# KarateLight-exp.net
KiCad netlist of a schematic drawn in EAGLE
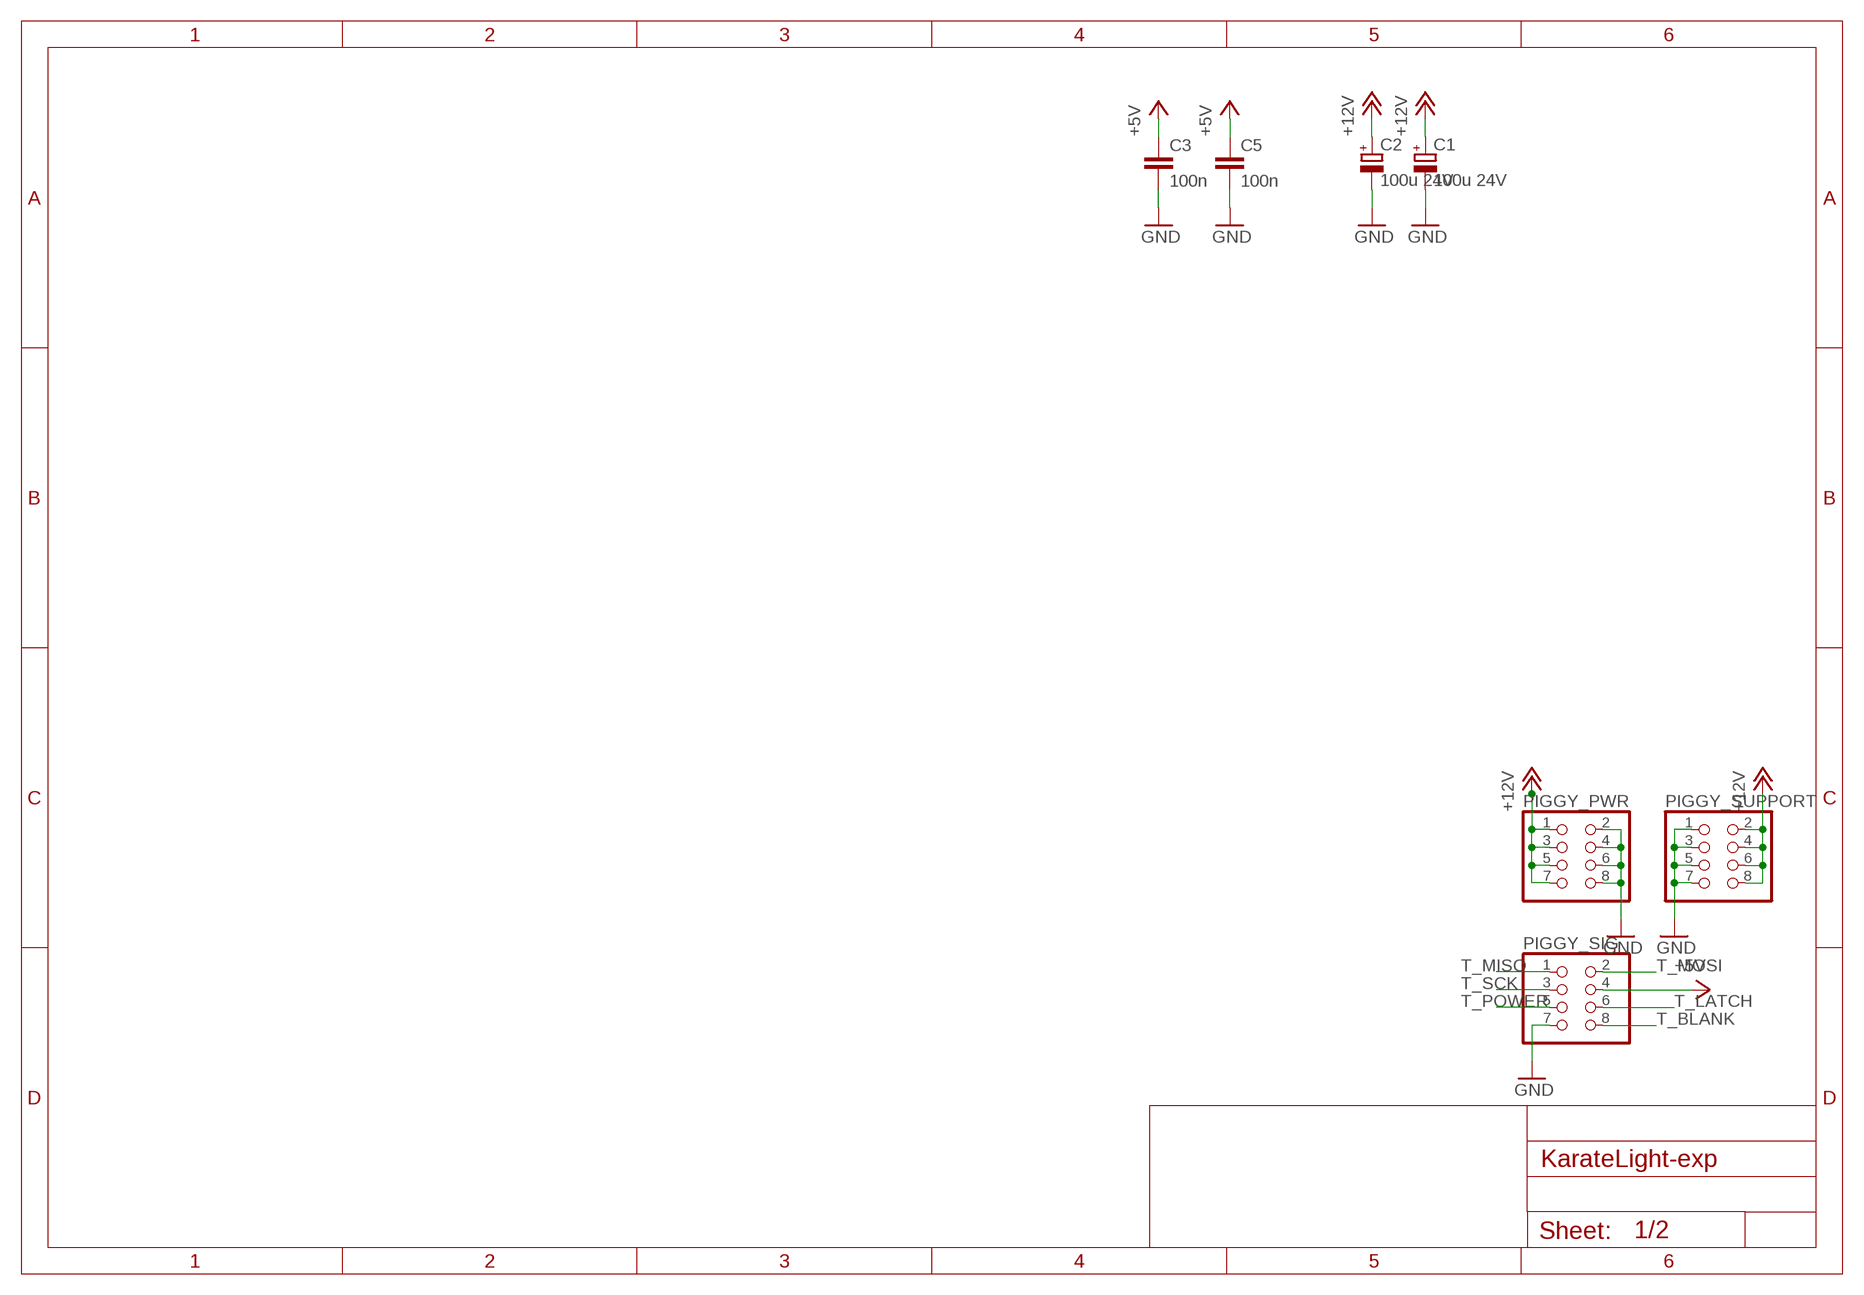
[diagram p0: schematic, sheet 1]
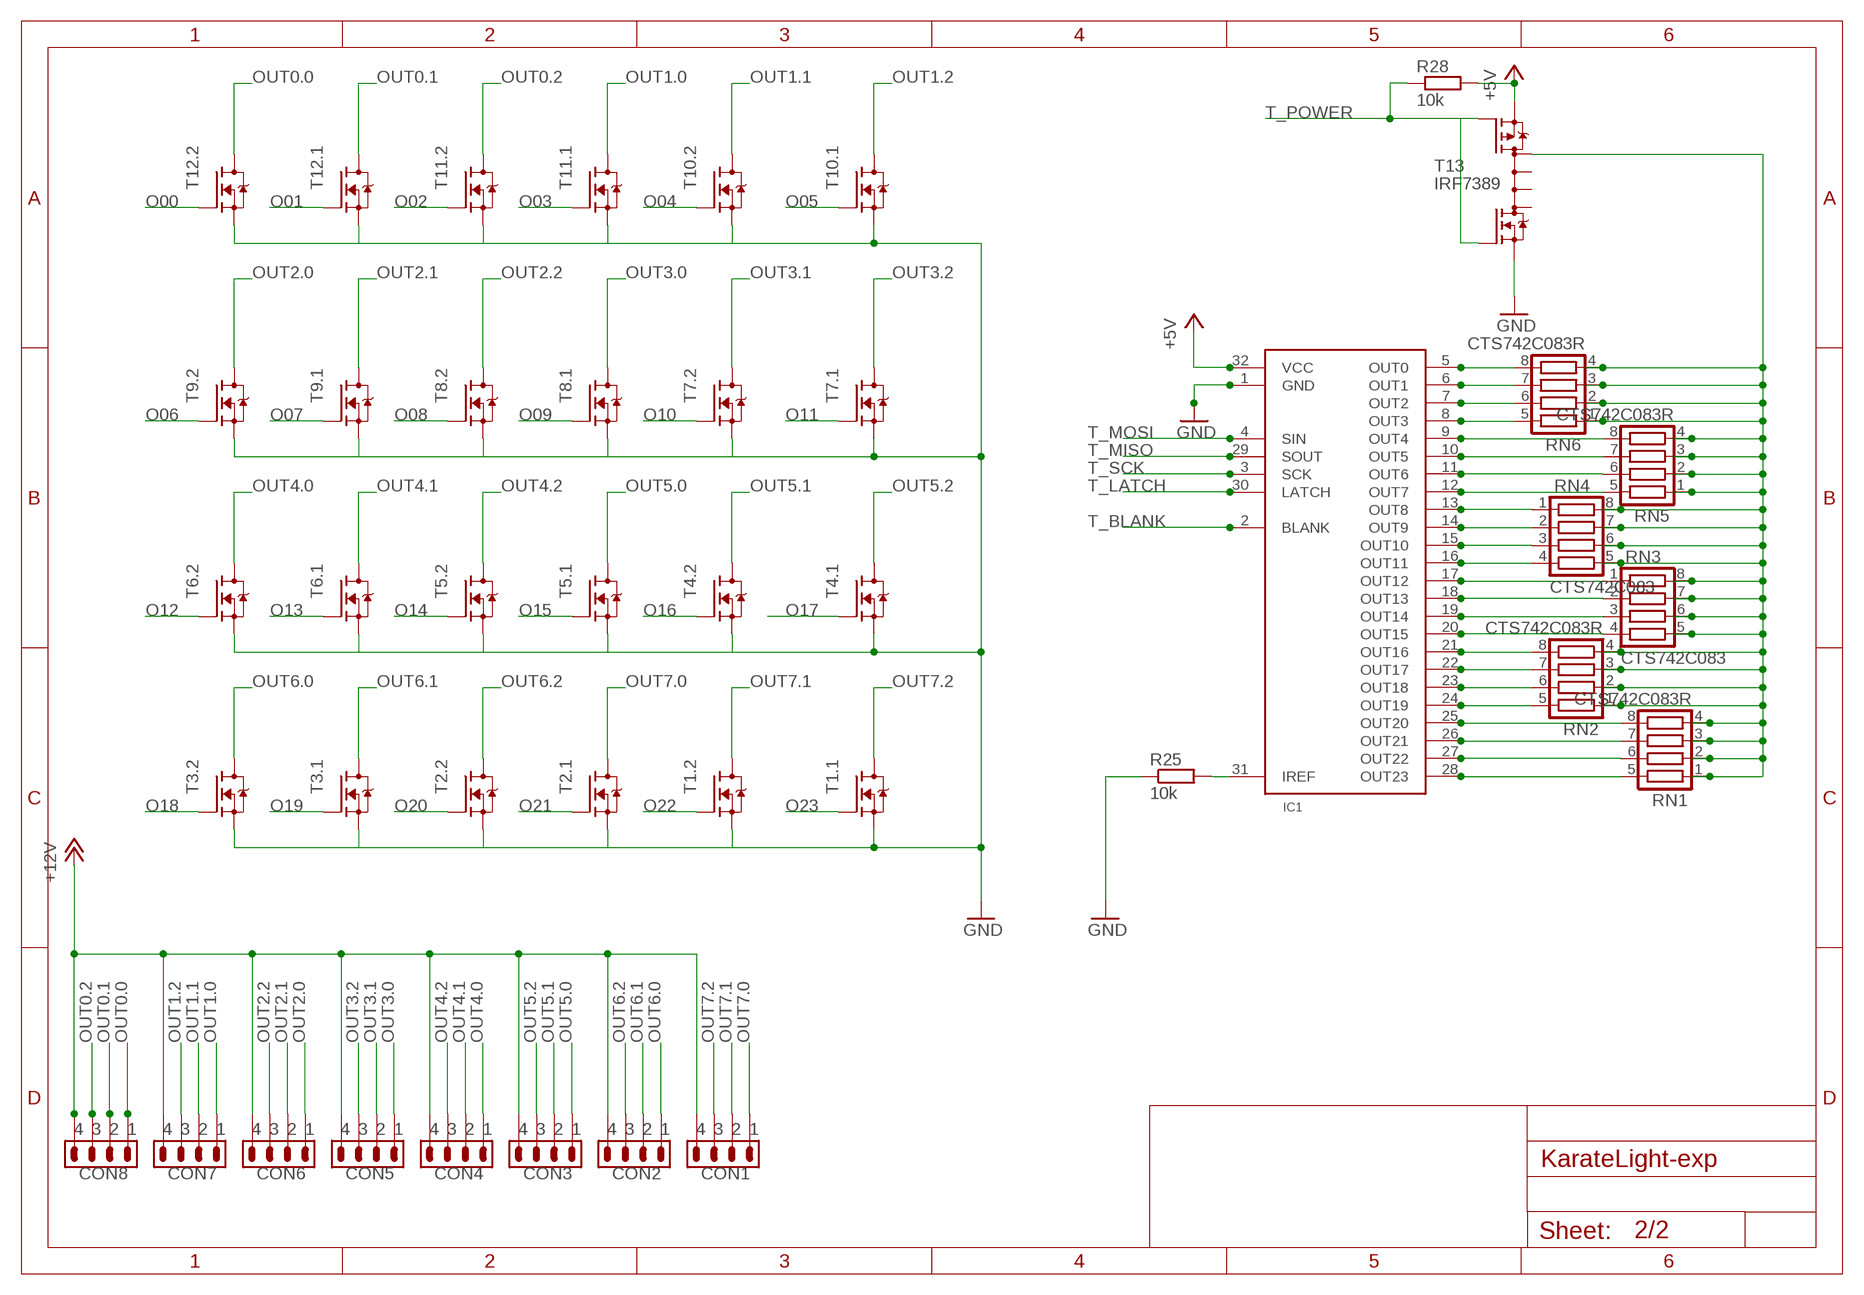
[diagram p1: schematic, sheet 2]

(export (version "E")
  (design (tool "Eeschema 10.0.6"))
  (components
    (comp (ref "CON1")
      (value "PINHEAD_4W")
      (footprint "eagle-import:MA04-1")
      (libsource (lib "eagle-import") (part "PINHEAD_4W"))
    )
    (comp (ref "CON2")
      (value "PINHEAD_4W")
      (footprint "eagle-import:MA04-1")
      (libsource (lib "eagle-import") (part "PINHEAD_4W"))
    )
    (comp (ref "CON3")
      (value "PINHEAD_4W")
      (footprint "eagle-import:MA04-1")
      (libsource (lib "eagle-import") (part "PINHEAD_4W"))
    )
    (comp (ref "CON4")
      (value "PINHEAD_4W")
      (footprint "eagle-import:MA04-1")
      (libsource (lib "eagle-import") (part "PINHEAD_4W"))
    )
    (comp (ref "CON5")
      (value "PINHEAD_4W")
      (footprint "eagle-import:MA04-1")
      (libsource (lib "eagle-import") (part "PINHEAD_4W"))
    )
    (comp (ref "CON6")
      (value "PINHEAD_4W")
      (footprint "eagle-import:MA04-1")
      (libsource (lib "eagle-import") (part "PINHEAD_4W"))
    )
    (comp (ref "CON7")
      (value "PINHEAD_4W")
      (footprint "eagle-import:MA04-1")
      (libsource (lib "eagle-import") (part "PINHEAD_4W"))
    )
    (comp (ref "CON8")
      (value "PINHEAD_4W")
      (footprint "eagle-import:MA04-1")
      (libsource (lib "eagle-import") (part "PINHEAD_4W"))
    )
    (comp (ref "IC1")
      (value "TLC5947")
      (footprint "eagle-import:TSSOP32")
      (libsource (lib "eagle-import") (part "TLC5947"))
    )
    (comp (ref "R25")
      (value "10k")
      (footprint "eagle-import:R0603")
      (libsource (lib "eagle-import") (part "R-EU_R0603"))
    )
    (comp (ref "R28")
      (value "10k")
      (footprint "eagle-import:R0603")
      (libsource (lib "eagle-import") (part "R-EU_R0603"))
    )
    (comp (ref "RN1")
      (value "CTS742C083R")
      (footprint "eagle-import:CTS742C083")
      (libsource (lib "eagle-import") (part "CTS742C083R"))
    )
    (comp (ref "RN2")
      (value "CTS742C083R")
      (footprint "eagle-import:CTS742C083")
      (libsource (lib "eagle-import") (part "CTS742C083R"))
    )
    (comp (ref "RN3")
      (value "CTS742C083")
      (footprint "eagle-import:CTS742C083")
      (fields (field (name "OC_FARNELL") "unknown") (field (name "OC_NEWARK") "unknown"))
      (libsource (lib "eagle-import") (part "CTS742C083"))
    )
    (comp (ref "RN4")
      (value "CTS742C083")
      (footprint "eagle-import:CTS742C083")
      (libsource (lib "eagle-import") (part "CTS742C083"))
    )
    (comp (ref "RN5")
      (value "CTS742C083R")
      (footprint "eagle-import:CTS742C083")
      (libsource (lib "eagle-import") (part "CTS742C083R"))
    )
    (comp (ref "RN6")
      (value "CTS742C083R")
      (footprint "eagle-import:CTS742C083")
      (libsource (lib "eagle-import") (part "CTS742C083R"))
    )
    (comp (ref "T1")
      (value "IRF7103")
      (footprint "eagle-import:SO08-IRF")
      (libsource (lib "eagle-import") (part "IRF7103"))
    )
    (comp (ref "T2")
      (value "IRF7103")
      (footprint "eagle-import:SO08-IRF")
      (libsource (lib "eagle-import") (part "IRF7103"))
    )
    (comp (ref "T3")
      (value "IRF7103")
      (footprint "eagle-import:SO08-IRF")
      (libsource (lib "eagle-import") (part "IRF7103"))
    )
    (comp (ref "T4")
      (value "IRF7103")
      (footprint "eagle-import:SO08-IRF")
      (libsource (lib "eagle-import") (part "IRF7103"))
    )
    (comp (ref "T5")
      (value "IRF7103")
      (footprint "eagle-import:SO08-IRF")
      (libsource (lib "eagle-import") (part "IRF7103"))
    )
    (comp (ref "T6")
      (value "IRF7103")
      (footprint "eagle-import:SO08-IRF")
      (libsource (lib "eagle-import") (part "IRF7103"))
    )
    (comp (ref "T7")
      (value "IRF7103")
      (footprint "eagle-import:SO08-IRF")
      (libsource (lib "eagle-import") (part "IRF7103"))
    )
    (comp (ref "T8")
      (value "IRF7103")
      (footprint "eagle-import:SO08-IRF")
      (libsource (lib "eagle-import") (part "IRF7103"))
    )
    (comp (ref "T9")
      (value "IRF7103")
      (footprint "eagle-import:SO08-IRF")
      (libsource (lib "eagle-import") (part "IRF7103"))
    )
    (comp (ref "T10")
      (value "IRF7103")
      (footprint "eagle-import:SO08-IRF")
      (libsource (lib "eagle-import") (part "IRF7103"))
    )
    (comp (ref "T11")
      (value "IRF7103")
      (footprint "eagle-import:SO08-IRF")
      (libsource (lib "eagle-import") (part "IRF7103"))
    )
    (comp (ref "T12")
      (value "IRF7103")
      (footprint "eagle-import:SO08-IRF")
      (libsource (lib "eagle-import") (part "IRF7103"))
    )
    (comp (ref "T13")
      (value "IRF7389")
      (footprint "eagle-import:SO08-IRF")
      (libsource (lib "eagle-import") (part "IRF7389"))
    )
    (comp (ref "C1")
      (value "100u 24V")
      (footprint "eagle-import:153CLV-0605")
      (libsource (lib "eagle-import") (part "CPOL-EU153CLV-0605"))
    )
    (comp (ref "C2")
      (value "100u 24V")
      (footprint "eagle-import:153CLV-0605")
      (libsource (lib "eagle-import") (part "CPOL-EU153CLV-0605"))
    )
    (comp (ref "C3")
      (value "100n")
      (footprint "eagle-import:C0603")
      (libsource (lib "eagle-import") (part "C-EUC0603"))
    )
    (comp (ref "C5")
      (value "100n")
      (footprint "eagle-import:C0603")
      (libsource (lib "eagle-import") (part "C-EUC0603"))
    )
    (comp (ref "PIGGY_PWR")
      (value "PINHD-2X4")
      (footprint "eagle-import:2X04")
      (libsource (lib "eagle-import") (part "PINHD-2X4"))
    )
    (comp (ref "PIGGY_SIG")
      (value "PINHD-2X4")
      (footprint "eagle-import:2X04")
      (libsource (lib "eagle-import") (part "PINHD-2X4"))
    )
    (comp (ref "PIGGY_SUPPORT")
      (value "PINHD-2X4")
      (footprint "eagle-import:2X04")
      (libsource (lib "eagle-import") (part "PINHD-2X4"))
    )
  )
  (nets
    (net (code "1") (name "+5V") (class "Default")
      (node (ref "C3") (pin "1") (pinfunction "1_1") (pintype "passive"))
      (node (ref "C5") (pin "1") (pinfunction "1_1") (pintype "passive"))
      (node (ref "IC1") (pin "32") (pinfunction "VCC_32") (pintype "bidirectional"))
      (node (ref "PIGGY_SIG") (pin "4") (pinfunction "4_4") (pintype "passive"))
      (node (ref "R28") (pin "2") (pinfunction "2_2") (pintype "passive"))
      (node (ref "T13") (pin "3") (pinfunction "P-S_3") (pintype "passive"))
    )
    (net (code "2") (name "+12V") (class "Default")
      (node (ref "C1") (pin "+") (pinfunction "+_+") (pintype "passive"))
      (node (ref "C2") (pin "+") (pinfunction "+_+") (pintype "passive"))
      (node (ref "CON1") (pin "4") (pinfunction "4_4") (pintype "bidirectional"))
      (node (ref "CON2") (pin "4") (pinfunction "4_4") (pintype "bidirectional"))
      (node (ref "CON3") (pin "4") (pinfunction "4_4") (pintype "bidirectional"))
      (node (ref "CON4") (pin "4") (pinfunction "4_4") (pintype "bidirectional"))
      (node (ref "CON5") (pin "4") (pinfunction "4_4") (pintype "bidirectional"))
      (node (ref "CON6") (pin "4") (pinfunction "4_4") (pintype "bidirectional"))
      (node (ref "CON7") (pin "4") (pinfunction "4_4") (pintype "bidirectional"))
      (node (ref "CON8") (pin "4") (pinfunction "4_4") (pintype "bidirectional"))
      (node (ref "PIGGY_PWR") (pin "1") (pinfunction "1_1") (pintype "passive"))
      (node (ref "PIGGY_PWR") (pin "3") (pinfunction "3_3") (pintype "passive"))
      (node (ref "PIGGY_PWR") (pin "5") (pinfunction "5_5") (pintype "passive"))
      (node (ref "PIGGY_PWR") (pin "7") (pinfunction "7_7") (pintype "passive"))
      (node (ref "PIGGY_SUPPORT") (pin "2") (pinfunction "2_2") (pintype "passive"))
      (node (ref "PIGGY_SUPPORT") (pin "4") (pinfunction "4_4") (pintype "passive"))
      (node (ref "PIGGY_SUPPORT") (pin "6") (pinfunction "6_6") (pintype "passive"))
      (node (ref "PIGGY_SUPPORT") (pin "8") (pinfunction "8_8") (pintype "passive"))
    )
    (net (code "3") (name "GND") (class "Default")
      (node (ref "C1") (pin "-") (pinfunction "-_-") (pintype "passive"))
      (node (ref "C2") (pin "-") (pinfunction "-_-") (pintype "passive"))
      (node (ref "C3") (pin "2") (pinfunction "2_2") (pintype "passive"))
      (node (ref "C5") (pin "2") (pinfunction "2_2") (pintype "passive"))
      (node (ref "IC1") (pin "1") (pinfunction "GND_1") (pintype "bidirectional"))
      (node (ref "PIGGY_PWR") (pin "2") (pinfunction "2_2") (pintype "passive"))
      (node (ref "PIGGY_PWR") (pin "4") (pinfunction "4_4") (pintype "passive"))
      (node (ref "PIGGY_PWR") (pin "6") (pinfunction "6_6") (pintype "passive"))
      (node (ref "PIGGY_PWR") (pin "8") (pinfunction "8_8") (pintype "passive"))
      (node (ref "PIGGY_SIG") (pin "7") (pinfunction "7_7") (pintype "passive"))
      (node (ref "PIGGY_SUPPORT") (pin "1") (pinfunction "1_1") (pintype "passive"))
      (node (ref "PIGGY_SUPPORT") (pin "3") (pinfunction "3_3") (pintype "passive"))
      (node (ref "PIGGY_SUPPORT") (pin "5") (pinfunction "5_5") (pintype "passive"))
      (node (ref "PIGGY_SUPPORT") (pin "7") (pinfunction "7_7") (pintype "passive"))
      (node (ref "R25") (pin "1") (pinfunction "1_1") (pintype "passive"))
      (node (ref "T1") (pin "1") (pinfunction "S_1") (pintype "passive"))
      (node (ref "T1") (pin "3") (pinfunction "S_3") (pintype "passive"))
      (node (ref "T10") (pin "1") (pinfunction "S_1") (pintype "passive"))
      (node (ref "T10") (pin "3") (pinfunction "S_3") (pintype "passive"))
      (node (ref "T11") (pin "1") (pinfunction "S_1") (pintype "passive"))
      (node (ref "T11") (pin "3") (pinfunction "S_3") (pintype "passive"))
      (node (ref "T12") (pin "1") (pinfunction "S_1") (pintype "passive"))
      (node (ref "T12") (pin "3") (pinfunction "S_3") (pintype "passive"))
      (node (ref "T13") (pin "1") (pinfunction "N-S_1") (pintype "passive"))
      (node (ref "T2") (pin "1") (pinfunction "S_1") (pintype "passive"))
      (node (ref "T2") (pin "3") (pinfunction "S_3") (pintype "passive"))
      (node (ref "T3") (pin "1") (pinfunction "S_1") (pintype "passive"))
      (node (ref "T3") (pin "3") (pinfunction "S_3") (pintype "passive"))
      (node (ref "T4") (pin "1") (pinfunction "S_1") (pintype "passive"))
      (node (ref "T4") (pin "3") (pinfunction "S_3") (pintype "passive"))
      (node (ref "T5") (pin "1") (pinfunction "S_1") (pintype "passive"))
      (node (ref "T5") (pin "3") (pinfunction "S_3") (pintype "passive"))
      (node (ref "T6") (pin "1") (pinfunction "S_1") (pintype "passive"))
      (node (ref "T6") (pin "3") (pinfunction "S_3") (pintype "passive"))
      (node (ref "T7") (pin "1") (pinfunction "S_1") (pintype "passive"))
      (node (ref "T7") (pin "3") (pinfunction "S_3") (pintype "passive"))
      (node (ref "T8") (pin "1") (pinfunction "S_1") (pintype "passive"))
      (node (ref "T8") (pin "3") (pinfunction "S_3") (pintype "passive"))
      (node (ref "T9") (pin "1") (pinfunction "S_1") (pintype "passive"))
      (node (ref "T9") (pin "3") (pinfunction "S_3") (pintype "passive"))
    )
    (net (code "4") (name "Net-(IC1-IREF)") (class "Default")
      (node (ref "IC1") (pin "31") (pinfunction "IREF_31") (pintype "bidirectional"))
      (node (ref "R25") (pin "2") (pinfunction "2_2") (pintype "passive"))
    )
    (net (code "5") (name "Net-(RN1-Pad1)") (class "Default")
      (node (ref "RN1") (pin "1") (pinfunction "1_1") (pintype "passive"))
      (node (ref "RN1") (pin "2") (pinfunction "2_2") (pintype "passive"))
      (node (ref "RN1") (pin "3") (pinfunction "3_3") (pintype "passive"))
      (node (ref "RN1") (pin "4") (pinfunction "4_4") (pintype "passive"))
      (node (ref "RN2") (pin "1") (pinfunction "1_1") (pintype "passive"))
      (node (ref "RN2") (pin "2") (pinfunction "2_2") (pintype "passive"))
      (node (ref "RN2") (pin "3") (pinfunction "3_3") (pintype "passive"))
      (node (ref "RN2") (pin "4") (pinfunction "4_4") (pintype "passive"))
      (node (ref "RN3") (pin "5") (pinfunction "5_5") (pintype "passive"))
      (node (ref "RN3") (pin "6") (pinfunction "6_6") (pintype "passive"))
      (node (ref "RN3") (pin "7") (pinfunction "7_7") (pintype "passive"))
      (node (ref "RN3") (pin "8") (pinfunction "8_8") (pintype "passive"))
      (node (ref "RN4") (pin "5") (pinfunction "5_5") (pintype "passive"))
      (node (ref "RN4") (pin "6") (pinfunction "6_6") (pintype "passive"))
      (node (ref "RN4") (pin "7") (pinfunction "7_7") (pintype "passive"))
      (node (ref "RN4") (pin "8") (pinfunction "8_8") (pintype "passive"))
      (node (ref "RN5") (pin "1") (pinfunction "1_1") (pintype "passive"))
      (node (ref "RN5") (pin "2") (pinfunction "2_2") (pintype "passive"))
      (node (ref "RN5") (pin "3") (pinfunction "3_3") (pintype "passive"))
      (node (ref "RN5") (pin "4") (pinfunction "4_4") (pintype "passive"))
      (node (ref "RN6") (pin "1") (pinfunction "1_1") (pintype "passive"))
      (node (ref "RN6") (pin "2") (pinfunction "2_2") (pintype "passive"))
      (node (ref "RN6") (pin "3") (pinfunction "3_3") (pintype "passive"))
      (node (ref "RN6") (pin "4") (pinfunction "4_4") (pintype "passive"))
      (node (ref "T13") (pin "5") (pinfunction "D_5") (pintype "passive"))
    )
    (net (code "6") (name "O00") (class "Default")
      (node (ref "IC1") (pin "5") (pinfunction "OUT0_5") (pintype "bidirectional"))
      (node (ref "RN6") (pin "8") (pinfunction "5_8") (pintype "passive"))
      (node (ref "T12") (pin "4") (pinfunction "G_4") (pintype "passive"))
    )
    (net (code "7") (name "O01") (class "Default")
      (node (ref "IC1") (pin "6") (pinfunction "OUT1_6") (pintype "bidirectional"))
      (node (ref "RN6") (pin "7") (pinfunction "6_7") (pintype "passive"))
      (node (ref "T12") (pin "2") (pinfunction "G_2") (pintype "passive"))
    )
    (net (code "8") (name "O02") (class "Default")
      (node (ref "IC1") (pin "7") (pinfunction "OUT2_7") (pintype "bidirectional"))
      (node (ref "RN6") (pin "6") (pinfunction "7_6") (pintype "passive"))
      (node (ref "T11") (pin "4") (pinfunction "G_4") (pintype "passive"))
    )
    (net (code "9") (name "O03") (class "Default")
      (node (ref "IC1") (pin "8") (pinfunction "OUT3_8") (pintype "bidirectional"))
      (node (ref "RN6") (pin "5") (pinfunction "8_5") (pintype "passive"))
      (node (ref "T11") (pin "2") (pinfunction "G_2") (pintype "passive"))
    )
    (net (code "10") (name "O04") (class "Default")
      (node (ref "IC1") (pin "9") (pinfunction "OUT4_9") (pintype "bidirectional"))
      (node (ref "RN5") (pin "8") (pinfunction "5_8") (pintype "passive"))
      (node (ref "T10") (pin "4") (pinfunction "G_4") (pintype "passive"))
    )
    (net (code "11") (name "O05") (class "Default")
      (node (ref "IC1") (pin "10") (pinfunction "OUT5_10") (pintype "bidirectional"))
      (node (ref "RN5") (pin "7") (pinfunction "6_7") (pintype "passive"))
      (node (ref "T10") (pin "2") (pinfunction "G_2") (pintype "passive"))
    )
    (net (code "12") (name "O06") (class "Default")
      (node (ref "IC1") (pin "11") (pinfunction "OUT6_11") (pintype "bidirectional"))
      (node (ref "RN5") (pin "6") (pinfunction "7_6") (pintype "passive"))
      (node (ref "T9") (pin "4") (pinfunction "G_4") (pintype "passive"))
    )
    (net (code "13") (name "O07") (class "Default")
      (node (ref "IC1") (pin "12") (pinfunction "OUT7_12") (pintype "bidirectional"))
      (node (ref "RN5") (pin "5") (pinfunction "8_5") (pintype "passive"))
      (node (ref "T9") (pin "2") (pinfunction "G_2") (pintype "passive"))
    )
    (net (code "14") (name "O08") (class "Default")
      (node (ref "IC1") (pin "13") (pinfunction "OUT8_13") (pintype "bidirectional"))
      (node (ref "RN4") (pin "1") (pinfunction "1_1") (pintype "passive"))
      (node (ref "T8") (pin "4") (pinfunction "G_4") (pintype "passive"))
    )
    (net (code "15") (name "O09") (class "Default")
      (node (ref "IC1") (pin "14") (pinfunction "OUT9_14") (pintype "bidirectional"))
      (node (ref "RN4") (pin "2") (pinfunction "2_2") (pintype "passive"))
      (node (ref "T8") (pin "2") (pinfunction "G_2") (pintype "passive"))
    )
    (net (code "16") (name "O10") (class "Default")
      (node (ref "IC1") (pin "15") (pinfunction "OUT10_15") (pintype "bidirectional"))
      (node (ref "RN4") (pin "3") (pinfunction "3_3") (pintype "passive"))
      (node (ref "T7") (pin "4") (pinfunction "G_4") (pintype "passive"))
    )
    (net (code "17") (name "O11") (class "Default")
      (node (ref "IC1") (pin "16") (pinfunction "OUT11_16") (pintype "bidirectional"))
      (node (ref "RN4") (pin "4") (pinfunction "4_4") (pintype "passive"))
      (node (ref "T7") (pin "2") (pinfunction "G_2") (pintype "passive"))
    )
    (net (code "18") (name "O12") (class "Default")
      (node (ref "IC1") (pin "17") (pinfunction "OUT12_17") (pintype "bidirectional"))
      (node (ref "RN3") (pin "1") (pinfunction "1_1") (pintype "passive"))
      (node (ref "T6") (pin "4") (pinfunction "G_4") (pintype "passive"))
    )
    (net (code "19") (name "O13") (class "Default")
      (node (ref "IC1") (pin "18") (pinfunction "OUT13_18") (pintype "bidirectional"))
      (node (ref "RN3") (pin "2") (pinfunction "2_2") (pintype "passive"))
      (node (ref "T6") (pin "2") (pinfunction "G_2") (pintype "passive"))
    )
    (net (code "20") (name "O14") (class "Default")
      (node (ref "IC1") (pin "19") (pinfunction "OUT14_19") (pintype "bidirectional"))
      (node (ref "RN3") (pin "3") (pinfunction "3_3") (pintype "passive"))
      (node (ref "T5") (pin "4") (pinfunction "G_4") (pintype "passive"))
    )
    (net (code "21") (name "O15") (class "Default")
      (node (ref "IC1") (pin "20") (pinfunction "OUT15_20") (pintype "bidirectional"))
      (node (ref "RN3") (pin "4") (pinfunction "4_4") (pintype "passive"))
      (node (ref "T5") (pin "2") (pinfunction "G_2") (pintype "passive"))
    )
    (net (code "22") (name "O16") (class "Default")
      (node (ref "IC1") (pin "21") (pinfunction "OUT16_21") (pintype "bidirectional"))
      (node (ref "RN2") (pin "8") (pinfunction "5_8") (pintype "passive"))
      (node (ref "T4") (pin "4") (pinfunction "G_4") (pintype "passive"))
    )
    (net (code "23") (name "O17") (class "Default")
      (node (ref "IC1") (pin "22") (pinfunction "OUT17_22") (pintype "bidirectional"))
      (node (ref "RN2") (pin "7") (pinfunction "6_7") (pintype "passive"))
      (node (ref "T4") (pin "2") (pinfunction "G_2") (pintype "passive"))
    )
    (net (code "24") (name "O18") (class "Default")
      (node (ref "IC1") (pin "23") (pinfunction "OUT18_23") (pintype "bidirectional"))
      (node (ref "RN2") (pin "6") (pinfunction "7_6") (pintype "passive"))
      (node (ref "T3") (pin "4") (pinfunction "G_4") (pintype "passive"))
    )
    (net (code "25") (name "O19") (class "Default")
      (node (ref "IC1") (pin "24") (pinfunction "OUT19_24") (pintype "bidirectional"))
      (node (ref "RN2") (pin "5") (pinfunction "8_5") (pintype "passive"))
      (node (ref "T3") (pin "2") (pinfunction "G_2") (pintype "passive"))
    )
    (net (code "26") (name "O20") (class "Default")
      (node (ref "IC1") (pin "25") (pinfunction "OUT20_25") (pintype "bidirectional"))
      (node (ref "RN1") (pin "8") (pinfunction "5_8") (pintype "passive"))
      (node (ref "T2") (pin "4") (pinfunction "G_4") (pintype "passive"))
    )
    (net (code "27") (name "O21") (class "Default")
      (node (ref "IC1") (pin "26") (pinfunction "OUT21_26") (pintype "bidirectional"))
      (node (ref "RN1") (pin "7") (pinfunction "6_7") (pintype "passive"))
      (node (ref "T2") (pin "2") (pinfunction "G_2") (pintype "passive"))
    )
    (net (code "28") (name "O22") (class "Default")
      (node (ref "IC1") (pin "27") (pinfunction "OUT22_27") (pintype "bidirectional"))
      (node (ref "RN1") (pin "6") (pinfunction "7_6") (pintype "passive"))
      (node (ref "T1") (pin "4") (pinfunction "G_4") (pintype "passive"))
    )
    (net (code "29") (name "O23") (class "Default")
      (node (ref "IC1") (pin "28") (pinfunction "OUT23_28") (pintype "bidirectional"))
      (node (ref "RN1") (pin "5") (pinfunction "8_5") (pintype "passive"))
      (node (ref "T1") (pin "2") (pinfunction "G_2") (pintype "passive"))
    )
    (net (code "30") (name "OUT0.0") (class "Default")
      (node (ref "CON8") (pin "1") (pinfunction "1_1") (pintype "bidirectional"))
      (node (ref "T12") (pin "6") (pinfunction "D_6") (pintype "passive"))
    )
    (net (code "31") (name "OUT0.1") (class "Default")
      (node (ref "CON8") (pin "2") (pinfunction "2_2") (pintype "bidirectional"))
      (node (ref "T12") (pin "8") (pinfunction "D_8") (pintype "passive"))
    )
    (net (code "32") (name "OUT0.2") (class "Default")
      (node (ref "CON8") (pin "3") (pinfunction "3_3") (pintype "bidirectional"))
      (node (ref "T11") (pin "6") (pinfunction "D_6") (pintype "passive"))
    )
    (net (code "33") (name "OUT1.0") (class "Default")
      (node (ref "CON7") (pin "1") (pinfunction "1_1") (pintype "bidirectional"))
      (node (ref "T11") (pin "8") (pinfunction "D_8") (pintype "passive"))
    )
    (net (code "34") (name "OUT1.1") (class "Default")
      (node (ref "CON7") (pin "2") (pinfunction "2_2") (pintype "bidirectional"))
      (node (ref "T10") (pin "6") (pinfunction "D_6") (pintype "passive"))
    )
    (net (code "35") (name "OUT1.2") (class "Default")
      (node (ref "CON7") (pin "3") (pinfunction "3_3") (pintype "bidirectional"))
      (node (ref "T10") (pin "8") (pinfunction "D_8") (pintype "passive"))
    )
    (net (code "36") (name "OUT2.0") (class "Default")
      (node (ref "CON6") (pin "1") (pinfunction "1_1") (pintype "bidirectional"))
      (node (ref "T9") (pin "6") (pinfunction "D_6") (pintype "passive"))
    )
    (net (code "37") (name "OUT2.1") (class "Default")
      (node (ref "CON6") (pin "2") (pinfunction "2_2") (pintype "bidirectional"))
      (node (ref "T9") (pin "8") (pinfunction "D_8") (pintype "passive"))
    )
    (net (code "38") (name "OUT2.2") (class "Default")
      (node (ref "CON6") (pin "3") (pinfunction "3_3") (pintype "bidirectional"))
      (node (ref "T8") (pin "6") (pinfunction "D_6") (pintype "passive"))
    )
    (net (code "39") (name "OUT3.0") (class "Default")
      (node (ref "CON5") (pin "1") (pinfunction "1_1") (pintype "bidirectional"))
      (node (ref "T8") (pin "8") (pinfunction "D_8") (pintype "passive"))
    )
    (net (code "40") (name "OUT3.1") (class "Default")
      (node (ref "CON5") (pin "2") (pinfunction "2_2") (pintype "bidirectional"))
      (node (ref "T7") (pin "6") (pinfunction "D_6") (pintype "passive"))
    )
    (net (code "41") (name "OUT3.2") (class "Default")
      (node (ref "CON5") (pin "3") (pinfunction "3_3") (pintype "bidirectional"))
      (node (ref "T7") (pin "8") (pinfunction "D_8") (pintype "passive"))
    )
    (net (code "42") (name "OUT4.0") (class "Default")
      (node (ref "CON4") (pin "1") (pinfunction "1_1") (pintype "bidirectional"))
      (node (ref "T6") (pin "6") (pinfunction "D_6") (pintype "passive"))
    )
    (net (code "43") (name "OUT4.1") (class "Default")
      (node (ref "CON4") (pin "2") (pinfunction "2_2") (pintype "bidirectional"))
      (node (ref "T6") (pin "8") (pinfunction "D_8") (pintype "passive"))
    )
    (net (code "44") (name "OUT4.2") (class "Default")
      (node (ref "CON4") (pin "3") (pinfunction "3_3") (pintype "bidirectional"))
      (node (ref "T5") (pin "6") (pinfunction "D_6") (pintype "passive"))
    )
    (net (code "45") (name "OUT5.0") (class "Default")
      (node (ref "CON3") (pin "1") (pinfunction "1_1") (pintype "bidirectional"))
      (node (ref "T5") (pin "8") (pinfunction "D_8") (pintype "passive"))
    )
    (net (code "46") (name "OUT5.1") (class "Default")
      (node (ref "CON3") (pin "2") (pinfunction "2_2") (pintype "bidirectional"))
      (node (ref "T4") (pin "6") (pinfunction "D_6") (pintype "passive"))
    )
    (net (code "47") (name "OUT5.2") (class "Default")
      (node (ref "CON3") (pin "3") (pinfunction "3_3") (pintype "bidirectional"))
      (node (ref "T4") (pin "8") (pinfunction "D_8") (pintype "passive"))
    )
    (net (code "48") (name "OUT6.0") (class "Default")
      (node (ref "CON2") (pin "1") (pinfunction "1_1") (pintype "bidirectional"))
      (node (ref "T3") (pin "6") (pinfunction "D_6") (pintype "passive"))
    )
    (net (code "49") (name "OUT6.1") (class "Default")
      (node (ref "CON2") (pin "2") (pinfunction "2_2") (pintype "bidirectional"))
      (node (ref "T3") (pin "8") (pinfunction "D_8") (pintype "passive"))
    )
    (net (code "50") (name "OUT6.2") (class "Default")
      (node (ref "CON2") (pin "3") (pinfunction "3_3") (pintype "bidirectional"))
      (node (ref "T2") (pin "6") (pinfunction "D_6") (pintype "passive"))
    )
    (net (code "51") (name "OUT7.0") (class "Default")
      (node (ref "CON1") (pin "1") (pinfunction "1_1") (pintype "bidirectional"))
      (node (ref "T2") (pin "8") (pinfunction "D_8") (pintype "passive"))
    )
    (net (code "52") (name "OUT7.1") (class "Default")
      (node (ref "CON1") (pin "2") (pinfunction "2_2") (pintype "bidirectional"))
      (node (ref "T1") (pin "6") (pinfunction "D_6") (pintype "passive"))
    )
    (net (code "53") (name "OUT7.2") (class "Default")
      (node (ref "CON1") (pin "3") (pinfunction "3_3") (pintype "bidirectional"))
      (node (ref "T1") (pin "8") (pinfunction "D_8") (pintype "passive"))
    )
    (net (code "54") (name "T_BLANK") (class "Default")
      (node (ref "IC1") (pin "2") (pinfunction "BLANK_2") (pintype "bidirectional"))
      (node (ref "PIGGY_SIG") (pin "8") (pinfunction "8_8") (pintype "passive"))
    )
    (net (code "55") (name "T_LATCH") (class "Default")
      (node (ref "IC1") (pin "30") (pinfunction "LATCH_30") (pintype "bidirectional"))
      (node (ref "PIGGY_SIG") (pin "6") (pinfunction "6_6") (pintype "passive"))
    )
    (net (code "56") (name "T_MISO") (class "Default")
      (node (ref "IC1") (pin "29") (pinfunction "SOUT_29") (pintype "bidirectional"))
      (node (ref "PIGGY_SIG") (pin "1") (pinfunction "1_1") (pintype "passive"))
    )
    (net (code "57") (name "T_MOSI") (class "Default")
      (node (ref "IC1") (pin "4") (pinfunction "SIN_4") (pintype "bidirectional"))
      (node (ref "PIGGY_SIG") (pin "2") (pinfunction "2_2") (pintype "passive"))
    )
    (net (code "58") (name "T_POWER") (class "Default")
      (node (ref "PIGGY_SIG") (pin "5") (pinfunction "5_5") (pintype "passive"))
      (node (ref "R28") (pin "1") (pinfunction "1_1") (pintype "passive"))
      (node (ref "T13") (pin "2") (pinfunction "N-G_2") (pintype "passive"))
      (node (ref "T13") (pin "4") (pinfunction "P-G_4") (pintype "passive"))
    )
    (net (code "59") (name "T_SCK") (class "Default")
      (node (ref "IC1") (pin "3") (pinfunction "SCK_3") (pintype "bidirectional"))
      (node (ref "PIGGY_SIG") (pin "3") (pinfunction "3_3") (pintype "passive"))
    )
    (net (code "60") (name "unconnected-(T13-D-Pad6)") (class "Default")
      (node (ref "T13") (pin "6") (pinfunction "D_6") (pintype "passive"))
    )
    (net (code "61") (name "unconnected-(T13-D-Pad7)") (class "Default")
      (node (ref "T13") (pin "7") (pinfunction "D_7") (pintype "passive"))
    )
    (net (code "62") (name "unconnected-(T13-D-Pad8)") (class "Default")
      (node (ref "T13") (pin "8") (pinfunction "D_8") (pintype "passive"))
    )
  )
)
